# lab_sist_dig.net
KiCad netlist of a schematic drawn in EAGLE
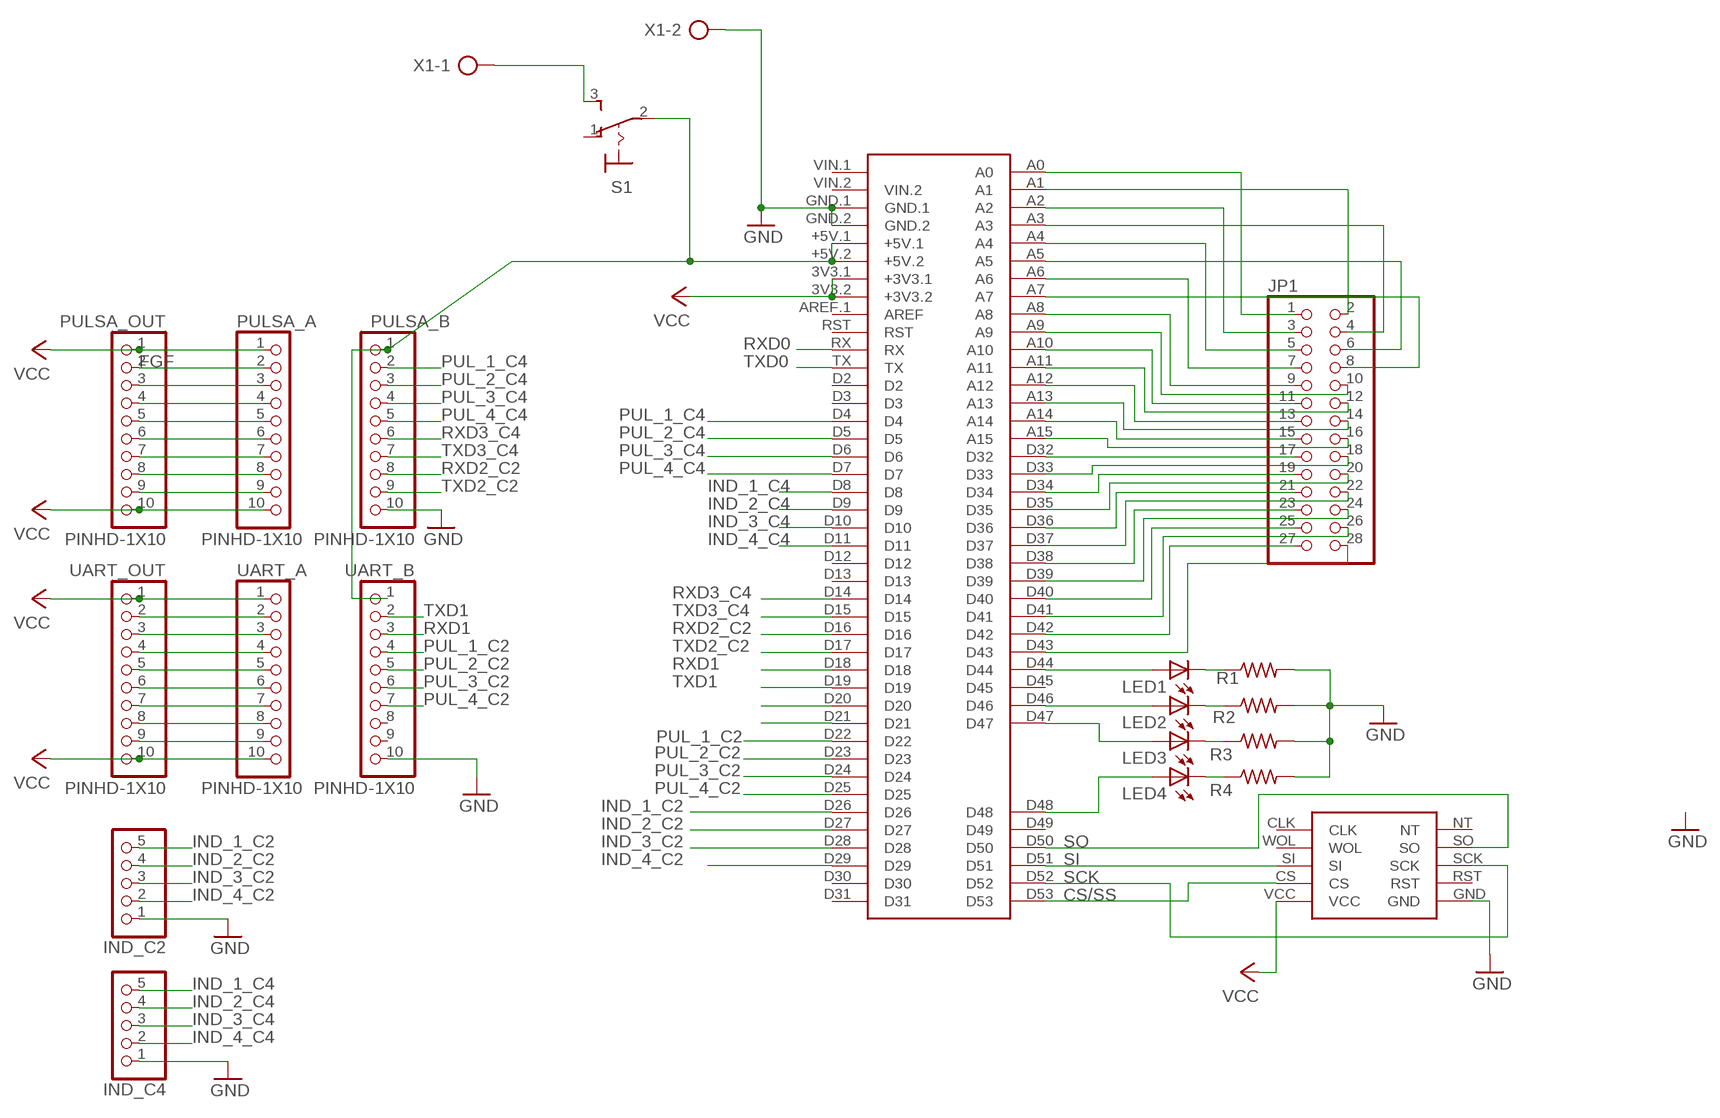
[diagram p0: schematic, sheet 1]

(export (version "E")
  (design (tool "Eeschema 10.0.6"))
  (components
    (comp (ref "IND_C2")
      (value "PINHD-1X5")
      (footprint "eagle-import:1X05")
      (libsource (lib "eagle-import") (part "PINHD-1X5"))
    )
    (comp (ref "IND_C4")
      (value "PINHD-1X5")
      (footprint "eagle-import:1X05")
      (libsource (lib "eagle-import") (part "PINHD-1X5"))
    )
    (comp (ref "JP1")
      (value "PINHD-2X14")
      (footprint "eagle-import:2X14")
      (libsource (lib "eagle-import") (part "PINHD-2X14"))
    )
    (comp (ref "LED1")
      (value "LED3MM")
      (footprint "eagle-import:LED3MM")
      (libsource (lib "eagle-import") (part "LED3MM"))
    )
    (comp (ref "LED2")
      (value "LED3MM")
      (footprint "eagle-import:LED3MM")
      (libsource (lib "eagle-import") (part "LED3MM"))
    )
    (comp (ref "LED3")
      (value "LED3MM")
      (footprint "eagle-import:LED3MM")
      (libsource (lib "eagle-import") (part "LED3MM"))
    )
    (comp (ref "LED4")
      (value "LED3MM")
      (footprint "eagle-import:LED3MM")
      (libsource (lib "eagle-import") (part "LED3MM"))
    )
    (comp (ref "PULSA_A")
      (value "PINHD-1X10")
      (footprint "eagle-import:1X10-BIG")
      (libsource (lib "eagle-import") (part "PINHD-1X10"))
    )
    (comp (ref "PULSA_B")
      (value "PINHD-1X10")
      (footprint "eagle-import:1X10-BIG")
      (libsource (lib "eagle-import") (part "PINHD-1X10"))
    )
    (comp (ref "PULSA_OUT")
      (value "PINHD-1X10")
      (footprint "eagle-import:1X10-BIG")
      (libsource (lib "eagle-import") (part "PINHD-1X10"))
    )
    (comp (ref "R1")
      (value "FLIPFLOP-RES")
      (footprint "eagle-import:0805-THM")
      (libsource (lib "eagle-import") (part "FLIPFLOP-RES"))
    )
    (comp (ref "R2")
      (value "FLIPFLOP-RES")
      (footprint "eagle-import:0805-THM")
      (libsource (lib "eagle-import") (part "FLIPFLOP-RES"))
    )
    (comp (ref "R3")
      (value "FLIPFLOP-RES")
      (footprint "eagle-import:0805-THM")
      (libsource (lib "eagle-import") (part "FLIPFLOP-RES"))
    )
    (comp (ref "R4")
      (value "FLIPFLOP-RES")
      (footprint "eagle-import:0805-THM")
      (libsource (lib "eagle-import") (part "FLIPFLOP-RES"))
    )
    (comp (ref "S1")
      (value "320-916")
      (footprint "eagle-import:320-916")
      (libsource (lib "eagle-import") (part "320-916"))
    )
    (comp (ref "U$1")
      (value "MEGA2560_MIKRO")
      (footprint "eagle-import:MEGA2560_MIKRO")
      (libsource (lib "eagle-import") (part "MEGA2560_MIKRO"))
    )
    (comp (ref "U$2")
      (value "ENC28J60")
      (footprint "eagle-import:ENC28J60")
      (libsource (lib "eagle-import") (part "ENC28J60"))
    )
    (comp (ref "UART_A")
      (value "PINHD-1X10")
      (footprint "eagle-import:1X10-BIG")
      (libsource (lib "eagle-import") (part "PINHD-1X10"))
    )
    (comp (ref "UART_B")
      (value "PINHD-1X10")
      (footprint "eagle-import:1X10-BIG")
      (libsource (lib "eagle-import") (part "PINHD-1X10"))
    )
    (comp (ref "UART_OUT")
      (value "PINHD-1X10")
      (footprint "eagle-import:1X10-BIG")
      (libsource (lib "eagle-import") (part "PINHD-1X10"))
    )
    (comp (ref "X1")
      (value "AK300/2")
      (footprint "eagle-import:AK300_2")
      (libsource (lib "eagle-import") (part "AK300/2"))
    )
  )
  (nets
    (net (code "1") (name "/CS{slash}SS") (class "Default")
      (node (ref "U$1") (pin "D53") (pinfunction "D53_D53") (pintype "bidirectional"))
      (node (ref "U$2") (pin "CS") (pinfunction "CS_CS") (pintype "bidirectional"))
    )
    (net (code "2") (name "/FGF") (class "Default")
      (node (ref "PULSA_A") (pin "2") (pinfunction "2_2") (pintype "passive"))
      (node (ref "PULSA_OUT") (pin "2") (pinfunction "2_2") (pintype "passive"))
    )
    (net (code "3") (name "/IND_1_C2") (class "Default")
      (node (ref "IND_C2") (pin "5") (pinfunction "5_5") (pintype "passive"))
      (node (ref "U$1") (pin "D26") (pinfunction "D26_D26") (pintype "bidirectional"))
    )
    (net (code "4") (name "/IND_1_C4") (class "Default")
      (node (ref "IND_C4") (pin "5") (pinfunction "5_5") (pintype "passive"))
      (node (ref "U$1") (pin "D8") (pinfunction "D8_D8") (pintype "bidirectional"))
    )
    (net (code "5") (name "/IND_2_C2") (class "Default")
      (node (ref "IND_C2") (pin "4") (pinfunction "4_4") (pintype "passive"))
      (node (ref "U$1") (pin "D27") (pinfunction "D27_D27") (pintype "bidirectional"))
    )
    (net (code "6") (name "/IND_2_C4") (class "Default")
      (node (ref "IND_C4") (pin "4") (pinfunction "4_4") (pintype "passive"))
      (node (ref "U$1") (pin "D9") (pinfunction "D9_D9") (pintype "bidirectional"))
    )
    (net (code "7") (name "/IND_3_C2") (class "Default")
      (node (ref "IND_C2") (pin "3") (pinfunction "3_3") (pintype "passive"))
      (node (ref "U$1") (pin "D28") (pinfunction "D28_D28") (pintype "bidirectional"))
    )
    (net (code "8") (name "/IND_3_C4") (class "Default")
      (node (ref "IND_C4") (pin "3") (pinfunction "3_3") (pintype "passive"))
      (node (ref "U$1") (pin "D10") (pinfunction "D10_D10") (pintype "bidirectional"))
    )
    (net (code "9") (name "/IND_4_C2") (class "Default")
      (node (ref "IND_C2") (pin "2") (pinfunction "2_2") (pintype "passive"))
      (node (ref "U$1") (pin "D29") (pinfunction "D29_D29") (pintype "bidirectional"))
    )
    (net (code "10") (name "/IND_4_C4") (class "Default")
      (node (ref "IND_C4") (pin "2") (pinfunction "2_2") (pintype "passive"))
      (node (ref "U$1") (pin "D11") (pinfunction "D11_D11") (pintype "bidirectional"))
    )
    (net (code "11") (name "/PUL_1_C2") (class "Default")
      (node (ref "U$1") (pin "D22") (pinfunction "D22_D22") (pintype "bidirectional"))
      (node (ref "UART_B") (pin "4") (pinfunction "4_4") (pintype "passive"))
    )
    (net (code "12") (name "/PUL_1_C4") (class "Default")
      (node (ref "PULSA_B") (pin "2") (pinfunction "2_2") (pintype "passive"))
      (node (ref "U$1") (pin "D4") (pinfunction "D4_D4") (pintype "bidirectional"))
    )
    (net (code "13") (name "/PUL_2_C2") (class "Default")
      (node (ref "U$1") (pin "D23") (pinfunction "D23_D23") (pintype "bidirectional"))
      (node (ref "UART_B") (pin "5") (pinfunction "5_5") (pintype "passive"))
    )
    (net (code "14") (name "/PUL_2_C4") (class "Default")
      (node (ref "PULSA_B") (pin "3") (pinfunction "3_3") (pintype "passive"))
      (node (ref "U$1") (pin "D5") (pinfunction "D5_D5") (pintype "bidirectional"))
    )
    (net (code "15") (name "/PUL_3_C2") (class "Default")
      (node (ref "U$1") (pin "D24") (pinfunction "D24_D24") (pintype "bidirectional"))
      (node (ref "UART_B") (pin "6") (pinfunction "6_6") (pintype "passive"))
    )
    (net (code "16") (name "/PUL_3_C4") (class "Default")
      (node (ref "PULSA_B") (pin "4") (pinfunction "4_4") (pintype "passive"))
      (node (ref "U$1") (pin "D6") (pinfunction "D6_D6") (pintype "bidirectional"))
    )
    (net (code "17") (name "/PUL_4_C2") (class "Default")
      (node (ref "U$1") (pin "D25") (pinfunction "D25_D25") (pintype "bidirectional"))
      (node (ref "UART_B") (pin "7") (pinfunction "7_7") (pintype "passive"))
    )
    (net (code "18") (name "/PUL_4_C4") (class "Default")
      (node (ref "PULSA_B") (pin "5") (pinfunction "5_5") (pintype "passive"))
      (node (ref "U$1") (pin "D7") (pinfunction "D7_D7") (pintype "bidirectional"))
    )
    (net (code "19") (name "/RXD0") (class "Default")
      (node (ref "U$1") (pin "RX") (pinfunction "RX_RX") (pintype "bidirectional"))
    )
    (net (code "20") (name "/RXD1") (class "Default")
      (node (ref "U$1") (pin "D18") (pinfunction "D18_D18") (pintype "bidirectional"))
      (node (ref "UART_B") (pin "3") (pinfunction "3_3") (pintype "passive"))
    )
    (net (code "21") (name "/RXD2_C2") (class "Default")
      (node (ref "PULSA_B") (pin "8") (pinfunction "8_8") (pintype "passive"))
      (node (ref "U$1") (pin "D16") (pinfunction "D16_D16") (pintype "bidirectional"))
    )
    (net (code "22") (name "/RXD3_C4") (class "Default")
      (node (ref "PULSA_B") (pin "6") (pinfunction "6_6") (pintype "passive"))
      (node (ref "U$1") (pin "D14") (pinfunction "D14_D14") (pintype "bidirectional"))
    )
    (net (code "23") (name "/SCK") (class "Default")
      (node (ref "U$1") (pin "D52") (pinfunction "D52_D52") (pintype "bidirectional"))
      (node (ref "U$2") (pin "SCK") (pinfunction "SCK_SCK") (pintype "bidirectional"))
    )
    (net (code "24") (name "/SI") (class "Default")
      (node (ref "U$1") (pin "D51") (pinfunction "D51_D51") (pintype "bidirectional"))
      (node (ref "U$2") (pin "SI") (pinfunction "SI_SI") (pintype "bidirectional"))
    )
    (net (code "25") (name "/SO") (class "Default")
      (node (ref "U$1") (pin "D50") (pinfunction "D50_D50") (pintype "bidirectional"))
      (node (ref "U$2") (pin "SO") (pinfunction "SO_SO") (pintype "bidirectional"))
    )
    (net (code "26") (name "/TXD0") (class "Default")
      (node (ref "U$1") (pin "TX") (pinfunction "TX_TX") (pintype "bidirectional"))
    )
    (net (code "27") (name "/TXD1") (class "Default")
      (node (ref "U$1") (pin "D19") (pinfunction "D19_D19") (pintype "bidirectional"))
      (node (ref "UART_B") (pin "2") (pinfunction "2_2") (pintype "passive"))
    )
    (net (code "28") (name "/TXD2_C2") (class "Default")
      (node (ref "PULSA_B") (pin "9") (pinfunction "9_9") (pintype "passive"))
      (node (ref "U$1") (pin "D17") (pinfunction "D17_D17") (pintype "bidirectional"))
    )
    (net (code "29") (name "/TXD3_C4") (class "Default")
      (node (ref "PULSA_B") (pin "7") (pinfunction "7_7") (pintype "passive"))
      (node (ref "U$1") (pin "D15") (pinfunction "D15_D15") (pintype "bidirectional"))
    )
    (net (code "30") (name "GND") (class "Default")
      (node (ref "IND_C2") (pin "1") (pinfunction "1_1") (pintype "passive"))
      (node (ref "IND_C4") (pin "1") (pinfunction "1_1") (pintype "passive"))
      (node (ref "PULSA_B") (pin "10") (pinfunction "10_10") (pintype "passive"))
      (node (ref "R1") (pin "2") (pinfunction "2_2") (pintype "passive"))
      (node (ref "R2") (pin "2") (pinfunction "2_2") (pintype "passive"))
      (node (ref "R3") (pin "2") (pinfunction "2_2") (pintype "passive"))
      (node (ref "R4") (pin "2") (pinfunction "2_2") (pintype "passive"))
      (node (ref "U$1") (pin "GND.1") (pinfunction "GND.1_GND.1") (pintype "bidirectional"))
      (node (ref "U$1") (pin "GND.2") (pinfunction "GND.2_GND.2") (pintype "bidirectional"))
      (node (ref "U$2") (pin "GND") (pinfunction "GND_GND") (pintype "bidirectional"))
      (node (ref "UART_B") (pin "10") (pinfunction "10_10") (pintype "passive"))
      (node (ref "X1") (pin "2") (pinfunction "KL_2") (pintype "passive"))
    )
    (net (code "31") (name "Net-(JP1-Pad1)") (class "Default")
      (node (ref "JP1") (pin "1") (pinfunction "1_1") (pintype "passive"))
      (node (ref "U$1") (pin "A0") (pinfunction "A0_A0") (pintype "bidirectional"))
    )
    (net (code "32") (name "Net-(JP1-Pad2)") (class "Default")
      (node (ref "JP1") (pin "2") (pinfunction "2_2") (pintype "passive"))
      (node (ref "U$1") (pin "A1") (pinfunction "A1_A1") (pintype "bidirectional"))
    )
    (net (code "33") (name "Net-(JP1-Pad3)") (class "Default")
      (node (ref "JP1") (pin "3") (pinfunction "3_3") (pintype "passive"))
      (node (ref "U$1") (pin "A2") (pinfunction "A2_A2") (pintype "bidirectional"))
    )
    (net (code "34") (name "Net-(JP1-Pad4)") (class "Default")
      (node (ref "JP1") (pin "4") (pinfunction "4_4") (pintype "passive"))
      (node (ref "U$1") (pin "A3") (pinfunction "A3_A3") (pintype "bidirectional"))
    )
    (net (code "35") (name "Net-(JP1-Pad5)") (class "Default")
      (node (ref "JP1") (pin "5") (pinfunction "5_5") (pintype "passive"))
      (node (ref "U$1") (pin "A4") (pinfunction "A4_A4") (pintype "bidirectional"))
    )
    (net (code "36") (name "Net-(JP1-Pad6)") (class "Default")
      (node (ref "JP1") (pin "6") (pinfunction "6_6") (pintype "passive"))
      (node (ref "U$1") (pin "A5") (pinfunction "A5_A5") (pintype "bidirectional"))
    )
    (net (code "37") (name "Net-(JP1-Pad7)") (class "Default")
      (node (ref "JP1") (pin "7") (pinfunction "7_7") (pintype "passive"))
      (node (ref "U$1") (pin "A6") (pinfunction "A6_A6") (pintype "bidirectional"))
    )
    (net (code "38") (name "Net-(JP1-Pad8)") (class "Default")
      (node (ref "JP1") (pin "8") (pinfunction "8_8") (pintype "passive"))
      (node (ref "U$1") (pin "A7") (pinfunction "A7_A7") (pintype "bidirectional"))
    )
    (net (code "39") (name "Net-(JP1-Pad9)") (class "Default")
      (node (ref "JP1") (pin "9") (pinfunction "9_9") (pintype "passive"))
      (node (ref "U$1") (pin "A8") (pinfunction "A8_A8") (pintype "bidirectional"))
    )
    (net (code "40") (name "Net-(JP1-Pad10)") (class "Default")
      (node (ref "JP1") (pin "10") (pinfunction "10_10") (pintype "passive"))
      (node (ref "U$1") (pin "A9") (pinfunction "A9_A9") (pintype "bidirectional"))
    )
    (net (code "41") (name "Net-(JP1-Pad11)") (class "Default")
      (node (ref "JP1") (pin "11") (pinfunction "11_11") (pintype "passive"))
      (node (ref "U$1") (pin "A10") (pinfunction "A10_A10") (pintype "bidirectional"))
    )
    (net (code "42") (name "Net-(JP1-Pad12)") (class "Default")
      (node (ref "JP1") (pin "12") (pinfunction "12_12") (pintype "passive"))
      (node (ref "U$1") (pin "A11") (pinfunction "A11_A11") (pintype "bidirectional"))
    )
    (net (code "43") (name "Net-(JP1-Pad13)") (class "Default")
      (node (ref "JP1") (pin "13") (pinfunction "13_13") (pintype "passive"))
      (node (ref "U$1") (pin "A12") (pinfunction "A12_A12") (pintype "bidirectional"))
    )
    (net (code "44") (name "Net-(JP1-Pad14)") (class "Default")
      (node (ref "JP1") (pin "14") (pinfunction "14_14") (pintype "passive"))
      (node (ref "U$1") (pin "A13") (pinfunction "A13_A13") (pintype "bidirectional"))
    )
    (net (code "45") (name "Net-(JP1-Pad15)") (class "Default")
      (node (ref "JP1") (pin "15") (pinfunction "15_15") (pintype "passive"))
      (node (ref "U$1") (pin "A14") (pinfunction "A14_A14") (pintype "bidirectional"))
    )
    (net (code "46") (name "Net-(JP1-Pad16)") (class "Default")
      (node (ref "JP1") (pin "16") (pinfunction "16_16") (pintype "passive"))
      (node (ref "U$1") (pin "A15") (pinfunction "A15_A15") (pintype "bidirectional"))
    )
    (net (code "47") (name "Net-(JP1-Pad17)") (class "Default")
      (node (ref "JP1") (pin "17") (pinfunction "17_17") (pintype "passive"))
      (node (ref "U$1") (pin "D32") (pinfunction "D32_D32") (pintype "bidirectional"))
    )
    (net (code "48") (name "Net-(JP1-Pad18)") (class "Default")
      (node (ref "JP1") (pin "18") (pinfunction "18_18") (pintype "passive"))
      (node (ref "U$1") (pin "D33") (pinfunction "D33_D33") (pintype "bidirectional"))
    )
    (net (code "49") (name "Net-(JP1-Pad19)") (class "Default")
      (node (ref "JP1") (pin "19") (pinfunction "19_19") (pintype "passive"))
      (node (ref "U$1") (pin "D34") (pinfunction "D34_D34") (pintype "bidirectional"))
    )
    (net (code "50") (name "Net-(JP1-Pad20)") (class "Default")
      (node (ref "JP1") (pin "20") (pinfunction "20_20") (pintype "passive"))
      (node (ref "U$1") (pin "D35") (pinfunction "D35_D35") (pintype "bidirectional"))
    )
    (net (code "51") (name "Net-(JP1-Pad21)") (class "Default")
      (node (ref "JP1") (pin "21") (pinfunction "21_21") (pintype "passive"))
      (node (ref "U$1") (pin "D36") (pinfunction "D36_D36") (pintype "bidirectional"))
    )
    (net (code "52") (name "Net-(JP1-Pad22)") (class "Default")
      (node (ref "JP1") (pin "22") (pinfunction "22_22") (pintype "passive"))
      (node (ref "U$1") (pin "D37") (pinfunction "D37_D37") (pintype "bidirectional"))
    )
    (net (code "53") (name "Net-(JP1-Pad23)") (class "Default")
      (node (ref "JP1") (pin "23") (pinfunction "23_23") (pintype "passive"))
      (node (ref "U$1") (pin "D38") (pinfunction "D38_D38") (pintype "bidirectional"))
    )
    (net (code "54") (name "Net-(JP1-Pad24)") (class "Default")
      (node (ref "JP1") (pin "24") (pinfunction "24_24") (pintype "passive"))
      (node (ref "U$1") (pin "D39") (pinfunction "D39_D39") (pintype "bidirectional"))
    )
    (net (code "55") (name "Net-(JP1-Pad25)") (class "Default")
      (node (ref "JP1") (pin "25") (pinfunction "25_25") (pintype "passive"))
      (node (ref "U$1") (pin "D40") (pinfunction "D40_D40") (pintype "bidirectional"))
    )
    (net (code "56") (name "Net-(JP1-Pad26)") (class "Default")
      (node (ref "JP1") (pin "26") (pinfunction "26_26") (pintype "passive"))
      (node (ref "U$1") (pin "D41") (pinfunction "D41_D41") (pintype "bidirectional"))
    )
    (net (code "57") (name "Net-(JP1-Pad27)") (class "Default")
      (node (ref "JP1") (pin "27") (pinfunction "27_27") (pintype "passive"))
      (node (ref "U$1") (pin "D42") (pinfunction "D42_D42") (pintype "bidirectional"))
    )
    (net (code "58") (name "Net-(JP1-Pad28)") (class "Default")
      (node (ref "JP1") (pin "28") (pinfunction "28_28") (pintype "passive"))
      (node (ref "U$1") (pin "D43") (pinfunction "D43_D43") (pintype "bidirectional"))
    )
    (net (code "59") (name "Net-(LED1-C)") (class "Default")
      (node (ref "LED1") (pin "K") (pinfunction "C_K") (pintype "passive"))
      (node (ref "R1") (pin "1") (pinfunction "1_1") (pintype "passive"))
    )
    (net (code "60") (name "Net-(LED1-PadA)") (class "Default")
      (node (ref "LED1") (pin "A") (pinfunction "A_A") (pintype "passive"))
      (node (ref "U$1") (pin "D44") (pinfunction "D44_D44") (pintype "bidirectional"))
    )
    (net (code "61") (name "Net-(LED2-C)") (class "Default")
      (node (ref "LED2") (pin "K") (pinfunction "C_K") (pintype "passive"))
      (node (ref "R2") (pin "1") (pinfunction "1_1") (pintype "passive"))
    )
    (net (code "62") (name "Net-(LED2-PadA)") (class "Default")
      (node (ref "LED2") (pin "A") (pinfunction "A_A") (pintype "passive"))
      (node (ref "U$1") (pin "D46") (pinfunction "D46_D46") (pintype "bidirectional"))
    )
    (net (code "63") (name "Net-(LED3-C)") (class "Default")
      (node (ref "LED3") (pin "K") (pinfunction "C_K") (pintype "passive"))
      (node (ref "R3") (pin "1") (pinfunction "1_1") (pintype "passive"))
    )
    (net (code "64") (name "Net-(LED3-PadA)") (class "Default")
      (node (ref "LED3") (pin "A") (pinfunction "A_A") (pintype "passive"))
      (node (ref "U$1") (pin "D47") (pinfunction "D47_D47") (pintype "bidirectional"))
    )
    (net (code "65") (name "Net-(LED4-C)") (class "Default")
      (node (ref "LED4") (pin "K") (pinfunction "C_K") (pintype "passive"))
      (node (ref "R4") (pin "1") (pinfunction "1_1") (pintype "passive"))
    )
    (net (code "66") (name "Net-(LED4-PadA)") (class "Default")
      (node (ref "LED4") (pin "A") (pinfunction "A_A") (pintype "passive"))
      (node (ref "U$1") (pin "D48") (pinfunction "D48_D48") (pintype "bidirectional"))
    )
    (net (code "67") (name "Net-(PULSA_A-Pad3)") (class "Default")
      (node (ref "PULSA_A") (pin "3") (pinfunction "3_3") (pintype "passive"))
      (node (ref "PULSA_OUT") (pin "3") (pinfunction "3_3") (pintype "passive"))
    )
    (net (code "68") (name "Net-(PULSA_A-Pad4)") (class "Default")
      (node (ref "PULSA_A") (pin "4") (pinfunction "4_4") (pintype "passive"))
      (node (ref "PULSA_OUT") (pin "4") (pinfunction "4_4") (pintype "passive"))
    )
    (net (code "69") (name "Net-(PULSA_A-Pad5)") (class "Default")
      (node (ref "PULSA_A") (pin "5") (pinfunction "5_5") (pintype "passive"))
      (node (ref "PULSA_OUT") (pin "5") (pinfunction "5_5") (pintype "passive"))
    )
    (net (code "70") (name "Net-(PULSA_A-Pad6)") (class "Default")
      (node (ref "PULSA_A") (pin "6") (pinfunction "6_6") (pintype "passive"))
      (node (ref "PULSA_OUT") (pin "6") (pinfunction "6_6") (pintype "passive"))
    )
    (net (code "71") (name "Net-(PULSA_A-Pad7)") (class "Default")
      (node (ref "PULSA_A") (pin "7") (pinfunction "7_7") (pintype "passive"))
      (node (ref "PULSA_OUT") (pin "7") (pinfunction "7_7") (pintype "passive"))
    )
    (net (code "72") (name "Net-(PULSA_A-Pad8)") (class "Default")
      (node (ref "PULSA_A") (pin "8") (pinfunction "8_8") (pintype "passive"))
      (node (ref "PULSA_OUT") (pin "8") (pinfunction "8_8") (pintype "passive"))
    )
    (net (code "73") (name "Net-(PULSA_A-Pad9)") (class "Default")
      (node (ref "PULSA_A") (pin "9") (pinfunction "9_9") (pintype "passive"))
      (node (ref "PULSA_OUT") (pin "9") (pinfunction "9_9") (pintype "passive"))
    )
    (net (code "74") (name "Net-(S1-P)") (class "Default")
      (node (ref "PULSA_B") (pin "1") (pinfunction "1_1") (pintype "passive"))
      (node (ref "S1") (pin "2") (pinfunction "P_2") (pintype "passive"))
      (node (ref "U$1") (pin "+5V.1") (pinfunction "+5V.1_+5V.1") (pintype "bidirectional"))
      (node (ref "U$1") (pin "+5V.2") (pinfunction "+5V.2_+5V.2") (pintype "bidirectional"))
      (node (ref "UART_B") (pin "1") (pinfunction "1_1") (pintype "passive"))
    )
    (net (code "75") (name "Net-(S1-S)") (class "Default")
      (node (ref "S1") (pin "3") (pinfunction "S_3") (pintype "passive"))
      (node (ref "X1") (pin "1") (pinfunction "KL_1") (pintype "passive"))
    )
    (net (code "76") (name "Net-(UART_A-Pad2)") (class "Default")
      (node (ref "UART_A") (pin "2") (pinfunction "2_2") (pintype "passive"))
      (node (ref "UART_OUT") (pin "2") (pinfunction "2_2") (pintype "passive"))
    )
    (net (code "77") (name "Net-(UART_A-Pad3)") (class "Default")
      (node (ref "UART_A") (pin "3") (pinfunction "3_3") (pintype "passive"))
      (node (ref "UART_OUT") (pin "3") (pinfunction "3_3") (pintype "passive"))
    )
    (net (code "78") (name "Net-(UART_A-Pad4)") (class "Default")
      (node (ref "UART_A") (pin "4") (pinfunction "4_4") (pintype "passive"))
      (node (ref "UART_OUT") (pin "4") (pinfunction "4_4") (pintype "passive"))
    )
    (net (code "79") (name "Net-(UART_A-Pad5)") (class "Default")
      (node (ref "UART_A") (pin "5") (pinfunction "5_5") (pintype "passive"))
      (node (ref "UART_OUT") (pin "5") (pinfunction "5_5") (pintype "passive"))
    )
    (net (code "80") (name "Net-(UART_A-Pad6)") (class "Default")
      (node (ref "UART_A") (pin "6") (pinfunction "6_6") (pintype "passive"))
      (node (ref "UART_OUT") (pin "6") (pinfunction "6_6") (pintype "passive"))
    )
    (net (code "81") (name "Net-(UART_A-Pad7)") (class "Default")
      (node (ref "UART_A") (pin "7") (pinfunction "7_7") (pintype "passive"))
      (node (ref "UART_OUT") (pin "7") (pinfunction "7_7") (pintype "passive"))
    )
    (net (code "82") (name "Net-(UART_A-Pad8)") (class "Default")
      (node (ref "UART_A") (pin "8") (pinfunction "8_8") (pintype "passive"))
      (node (ref "UART_OUT") (pin "8") (pinfunction "8_8") (pintype "passive"))
    )
    (net (code "83") (name "Net-(UART_A-Pad9)") (class "Default")
      (node (ref "UART_A") (pin "9") (pinfunction "9_9") (pintype "passive"))
      (node (ref "UART_OUT") (pin "9") (pinfunction "9_9") (pintype "passive"))
    )
    (net (code "84") (name "VCC") (class "Default")
      (node (ref "PULSA_A") (pin "1") (pinfunction "1_1") (pintype "passive"))
      (node (ref "PULSA_A") (pin "10") (pinfunction "10_10") (pintype "passive"))
      (node (ref "PULSA_OUT") (pin "1") (pinfunction "1_1") (pintype "passive"))
      (node (ref "PULSA_OUT") (pin "10") (pinfunction "10_10") (pintype "passive"))
      (node (ref "U$1") (pin "3V3.1") (pinfunction "+3V3.1_3V3.1") (pintype "bidirectional"))
      (node (ref "U$1") (pin "3V3.2") (pinfunction "+3V3.2_3V3.2") (pintype "bidirectional"))
      (node (ref "U$2") (pin "VCC") (pinfunction "VCC_VCC") (pintype "bidirectional"))
      (node (ref "UART_A") (pin "1") (pinfunction "1_1") (pintype "passive"))
      (node (ref "UART_A") (pin "10") (pinfunction "10_10") (pintype "passive"))
      (node (ref "UART_OUT") (pin "1") (pinfunction "1_1") (pintype "passive"))
      (node (ref "UART_OUT") (pin "10") (pinfunction "10_10") (pintype "passive"))
    )
    (net (code "85") (name "unconnected-(S1-O-Pad1)") (class "Default")
      (node (ref "S1") (pin "1") (pinfunction "O_1") (pintype "passive"))
    )
    (net (code "86") (name "unconnected-(U$1-AREF-PadAREF.1)") (class "Default")
      (node (ref "U$1") (pin "AREF.1") (pinfunction "AREF_AREF.1") (pintype "bidirectional"))
    )
    (net (code "87") (name "unconnected-(U$1-PadD2)") (class "Default")
      (node (ref "U$1") (pin "D2") (pinfunction "D2_D2") (pintype "bidirectional"))
    )
    (net (code "88") (name "unconnected-(U$1-PadD3)") (class "Default")
      (node (ref "U$1") (pin "D3") (pinfunction "D3_D3") (pintype "bidirectional"))
    )
    (net (code "89") (name "unconnected-(U$1-PadD12)") (class "Default")
      (node (ref "U$1") (pin "D12") (pinfunction "D12_D12") (pintype "bidirectional"))
    )
    (net (code "90") (name "unconnected-(U$1-PadD13)") (class "Default")
      (node (ref "U$1") (pin "D13") (pinfunction "D13_D13") (pintype "bidirectional"))
    )
    (net (code "91") (name "unconnected-(U$1-PadD20)") (class "Default")
      (node (ref "U$1") (pin "D20") (pinfunction "D20_D20") (pintype "bidirectional"))
    )
    (net (code "92") (name "unconnected-(U$1-PadD21)") (class "Default")
      (node (ref "U$1") (pin "D21") (pinfunction "D21_D21") (pintype "bidirectional"))
    )
    (net (code "93") (name "unconnected-(U$1-PadD30)") (class "Default")
      (node (ref "U$1") (pin "D30") (pinfunction "D30_D30") (pintype "bidirectional"))
    )
    (net (code "94") (name "unconnected-(U$1-PadD31)") (class "Default")
      (node (ref "U$1") (pin "D31") (pinfunction "D31_D31") (pintype "bidirectional"))
    )
    (net (code "95") (name "unconnected-(U$1-PadD45)") (class "Default")
      (node (ref "U$1") (pin "D45") (pinfunction "D45_D45") (pintype "bidirectional"))
    )
    (net (code "96") (name "unconnected-(U$1-PadD49)") (class "Default")
      (node (ref "U$1") (pin "D49") (pinfunction "D49_D49") (pintype "bidirectional"))
    )
    (net (code "97") (name "unconnected-(U$1-PadRST)") (class "Default")
      (node (ref "U$1") (pin "RST") (pinfunction "RST_RST") (pintype "bidirectional"))
    )
    (net (code "98") (name "unconnected-(U$1-PadVIN.1)") (class "Default")
      (node (ref "U$1") (pin "VIN.1") (pinfunction "VIN.1_VIN.1") (pintype "bidirectional"))
    )
    (net (code "99") (name "unconnected-(U$1-PadVIN.2)") (class "Default")
      (node (ref "U$1") (pin "VIN.2") (pinfunction "VIN.2_VIN.2") (pintype "bidirectional"))
    )
    (net (code "100") (name "unconnected-(U$2-PadCLK)") (class "Default")
      (node (ref "U$2") (pin "CLK") (pinfunction "CLK_CLK") (pintype "bidirectional"))
    )
    (net (code "101") (name "unconnected-(U$2-PadNT)") (class "Default")
      (node (ref "U$2") (pin "NT") (pinfunction "NT_NT") (pintype "bidirectional"))
    )
    (net (code "102") (name "unconnected-(U$2-PadRST)") (class "Default")
      (node (ref "U$2") (pin "RST") (pinfunction "RST_RST") (pintype "bidirectional"))
    )
    (net (code "103") (name "unconnected-(U$2-PadWOL)") (class "Default")
      (node (ref "U$2") (pin "WOL") (pinfunction "WOL_WOL") (pintype "bidirectional"))
    )
    (net (code "104") (name "unconnected-(UART_B-Pad8)") (class "Default")
      (node (ref "UART_B") (pin "8") (pinfunction "8_8") (pintype "passive"))
    )
    (net (code "105") (name "unconnected-(UART_B-Pad9)") (class "Default")
      (node (ref "UART_B") (pin "9") (pinfunction "9_9") (pintype "passive"))
    )
  )
)
